# SAMV71_Xplained_Ultra_Shield_Connectors.net
KiCad netlist of a schematic drawn in Altium Designer
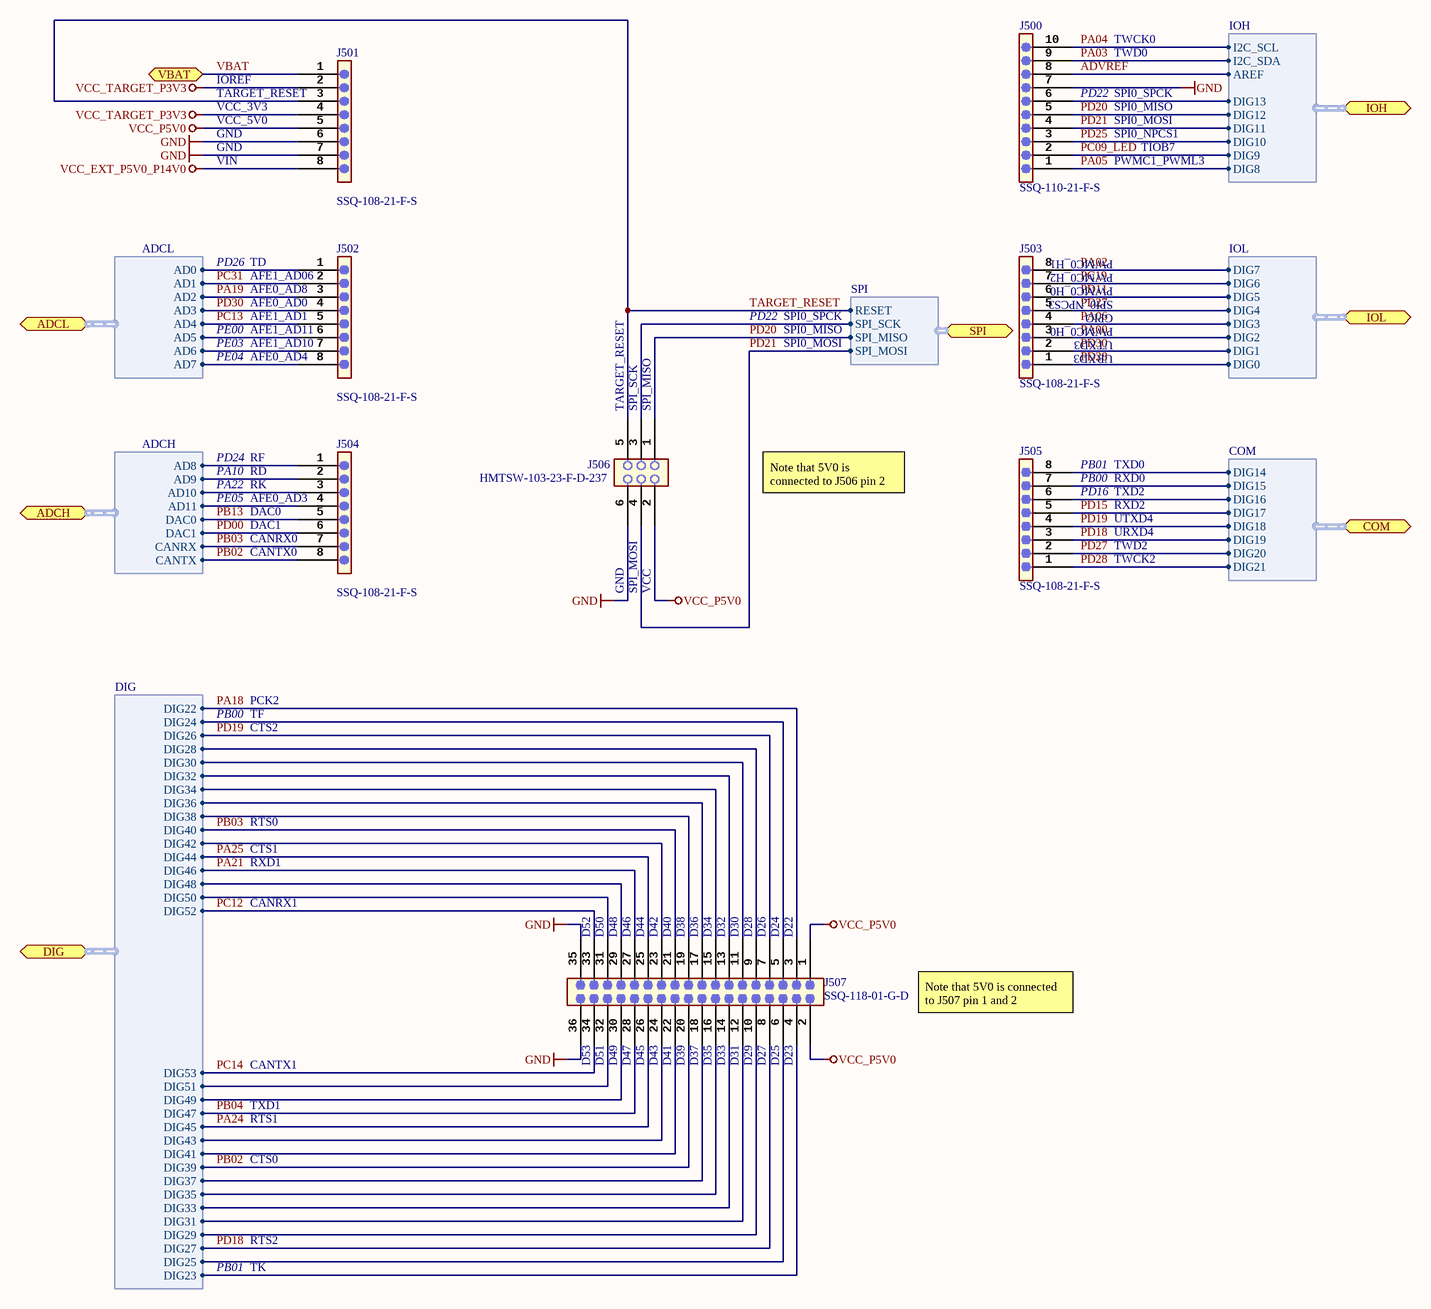
[diagram p0: SAMV71_Xplained_Ultra_Shield_Connectors.SchDoc]

(export (version "E")
  (design (tool "Eeschema 10.0.6"))
  (components
    (comp (ref "J500")
      (value "SSQ-110-21-F-S")
      (footprint "AP8-00822")
      (description "1x10 receptacle pin header, low insertion force, 2.54mm pitch THM, Pin in Paste")
      (fields (field (name "MANUFACTURER") "SAMTEC"))
      (libsource (lib "AltiumDbLib") (part "HEADER 1x10 FEMALE"))
    )
    (comp (ref "J501")
      (value "SSQ-108-21-F-S")
      (footprint "AP8-00823")
      (description "1x8 receptacle pin header, low insertion force, 2.54mm pitch THM, Pin in Paste")
      (fields (field (name "MANUFACTURER") "SAMTEC"))
      (libsource (lib "") (part "HEADER 1x8 FEMALE_1"))
    )
    (comp (ref "J502")
      (value "SSQ-108-21-F-S")
      (footprint "AP8-00823")
      (description "1x8 receptacle pin header, low insertion force, 2.54mm pitch THM, Pin in Paste")
      (fields (field (name "MANUFACTURER") "SAMTEC"))
      (libsource (lib "") (part "HEADER 1x8 FEMALE_1"))
    )
    (comp (ref "J503")
      (value "SSQ-108-21-F-S")
      (footprint "AP8-00823")
      (description "1x8 receptacle pin header, low insertion force, 2.54mm pitch THM, Pin in Paste")
      (fields (field (name "MANUFACTURER") "SAMTEC"))
      (libsource (lib "AltiumDbLib") (part "HEADER 1x8 FEMALE"))
    )
    (comp (ref "J504")
      (value "SSQ-108-21-F-S")
      (footprint "AP8-00823")
      (description "1x8 receptacle pin header, low insertion force, 2.54mm pitch THM, Pin in Paste")
      (fields (field (name "MANUFACTURER") "SAMTEC"))
      (libsource (lib "") (part "HEADER 1x8 FEMALE_1"))
    )
    (comp (ref "J505")
      (value "SSQ-108-21-F-S")
      (footprint "AP8-00823")
      (description "1x8 receptacle pin header, low insertion force, 2.54mm pitch THM, Pin in Paste")
      (fields (field (name "MANUFACTURER") "SAMTEC"))
      (libsource (lib "AltiumDbLib") (part "HEADER 1x8 FEMALE"))
    )
    (comp (ref "J506")
      (value "HMTSW-103-23-F-D-237")
      (footprint "AP8-00182")
      (description "2x3 pin header, 2.54mm pitch, Pin-in-Paste THM")
      (fields (field (name "MANUFACTURER") "SAMTEC"))
      (libsource (lib "AltiumDbLib") (part "HEADER 2x3"))
    )
    (comp (ref "J507")
      (value "SSQ-118-01-G-D")
      (footprint "AP8-00259")
      (description "2x18 female pin header, 2.54mm pitch, THM")
      (fields (field (name "MANUFACTURER") "SAMTEC"))
      (libsource (lib "AltiumDbLib") (part "HEADER 2x18 FEMALE"))
    )
  )
  (nets
    (net (code "8") (name "/AD0") (class "Default")
      (node (ref "J502") (pin "1") (pinfunction "1_1") (pintype "passive"))
    )
    (net (code "9") (name "/AD5") (class "Default")
      (node (ref "J502") (pin "6") (pinfunction "6_6") (pintype "passive"))
    )
    (net (code "10") (name "/AD6") (class "Default")
      (node (ref "J502") (pin "7") (pinfunction "7_7") (pintype "passive"))
    )
    (net (code "11") (name "/AD7") (class "Default")
      (node (ref "J502") (pin "8") (pinfunction "8_8") (pintype "passive"))
    )
    (net (code "12") (name "/AD8") (class "Default")
      (node (ref "J504") (pin "1") (pinfunction "1_1") (pintype "passive"))
    )
    (net (code "13") (name "/AD9") (class "Default")
      (node (ref "J504") (pin "2") (pinfunction "2_2") (pintype "passive"))
    )
    (net (code "14") (name "/AD10") (class "Default")
      (node (ref "J504") (pin "3") (pinfunction "3_3") (pintype "passive"))
    )
    (net (code "15") (name "/AD11") (class "Default")
      (node (ref "J504") (pin "4") (pinfunction "4_4") (pintype "passive"))
    )
    (net (code "16") (name "/ADVREF") (class "Default")
      (node (ref "J500") (pin "8") (pinfunction "8_8") (pintype "passive"))
    )
    (net (code "17") (name "/DIG13") (class "Default")
      (node (ref "J500") (pin "6") (pinfunction "6_6") (pintype "passive"))
    )
    (net (code "18") (name "/DIG14") (class "Default")
      (node (ref "J505") (pin "8") (pinfunction "8_8") (pintype "passive"))
    )
    (net (code "19") (name "/DIG15") (class "Default")
      (node (ref "J505") (pin "7") (pinfunction "7_7") (pintype "passive"))
    )
    (net (code "20") (name "/DIG16") (class "Default")
      (node (ref "J505") (pin "6") (pinfunction "6_6") (pintype "passive"))
    )
    (net (code "21") (name "/DIG23") (class "Default")
      (node (ref "J507") (pin "4") (pinfunction "4_4") (pintype "passive"))
    )
    (net (code "22") (name "/DIG24") (class "Default")
      (node (ref "J507") (pin "5") (pinfunction "5_5") (pintype "passive"))
    )
    (net (code "23") (name "/DIG25") (class "Default")
      (node (ref "J507") (pin "6") (pinfunction "6_6") (pintype "passive"))
    )
    (net (code "24") (name "/DIG28") (class "Default")
      (node (ref "J507") (pin "9") (pinfunction "9_9") (pintype "passive"))
    )
    (net (code "25") (name "/DIG29") (class "Default")
      (node (ref "J507") (pin "10") (pinfunction "10_10") (pintype "passive"))
    )
    (net (code "26") (name "/DIG30") (class "Default")
      (node (ref "J507") (pin "11") (pinfunction "11_11") (pintype "passive"))
    )
    (net (code "27") (name "/DIG31") (class "Default")
      (node (ref "J507") (pin "12") (pinfunction "12_12") (pintype "passive"))
    )
    (net (code "28") (name "/DIG32") (class "Default")
      (node (ref "J507") (pin "13") (pinfunction "13_13") (pintype "passive"))
    )
    (net (code "29") (name "/DIG33") (class "Default")
      (node (ref "J507") (pin "14") (pinfunction "14_14") (pintype "passive"))
    )
    (net (code "30") (name "/DIG34") (class "Default")
      (node (ref "J507") (pin "15") (pinfunction "15_15") (pintype "passive"))
    )
    (net (code "31") (name "/DIG35") (class "Default")
      (node (ref "J507") (pin "16") (pinfunction "16_16") (pintype "passive"))
    )
    (net (code "32") (name "/DIG36") (class "Default")
      (node (ref "J507") (pin "17") (pinfunction "17_17") (pintype "passive"))
    )
    (net (code "33") (name "/DIG37") (class "Default")
      (node (ref "J507") (pin "18") (pinfunction "18_18") (pintype "passive"))
    )
    (net (code "34") (name "/DIG38") (class "Default")
      (node (ref "J507") (pin "19") (pinfunction "19_19") (pintype "passive"))
    )
    (net (code "35") (name "/DIG41") (class "Default")
      (node (ref "J507") (pin "22") (pinfunction "22_22") (pintype "passive"))
    )
    (net (code "36") (name "/DIG42") (class "Default")
      (node (ref "J507") (pin "23") (pinfunction "23_23") (pintype "passive"))
    )
    (net (code "37") (name "/DIG43") (class "Default")
      (node (ref "J507") (pin "24") (pinfunction "24_24") (pintype "passive"))
    )
    (net (code "38") (name "/DIG48") (class "Default")
      (node (ref "J507") (pin "29") (pinfunction "29_29") (pintype "passive"))
    )
    (net (code "39") (name "/DIG49") (class "Default")
      (node (ref "J507") (pin "30") (pinfunction "30_30") (pintype "passive"))
    )
    (net (code "40") (name "/DIG50") (class "Default")
      (node (ref "J507") (pin "31") (pinfunction "31_31") (pintype "passive"))
    )
    (net (code "41") (name "/DIG51") (class "Default")
      (node (ref "J507") (pin "32") (pinfunction "32_32") (pintype "passive"))
    )
    (net (code "42") (name "/PA00") (class "Default")
      (node (ref "J503") (pin "3") (pinfunction "3_3") (pintype "passive"))
    )
    (net (code "43") (name "/PA02") (class "Default")
      (node (ref "J503") (pin "8") (pinfunction "8_8") (pintype "passive"))
    )
    (net (code "44") (name "/PA03") (class "Default")
      (node (ref "J500") (pin "9") (pinfunction "9_9") (pintype "passive"))
    )
    (net (code "45") (name "/PA04") (class "Default")
      (node (ref "J500") (pin "10") (pinfunction "10_10") (pintype "passive"))
    )
    (net (code "46") (name "/PA05") (class "Default")
      (node (ref "J500") (pin "1") (pinfunction "1_1") (pintype "passive"))
    )
    (net (code "47") (name "/PA06") (class "Default")
      (node (ref "J503") (pin "4") (pinfunction "4_4") (pintype "passive"))
    )
    (net (code "48") (name "/PA18") (class "Default")
      (node (ref "J507") (pin "3") (pinfunction "3_3") (pintype "passive"))
    )
    (net (code "49") (name "/PA19") (class "Default")
      (node (ref "J502") (pin "3") (pinfunction "3_3") (pintype "passive"))
    )
    (net (code "50") (name "/PA21") (class "Default")
      (node (ref "J507") (pin "27") (pinfunction "27_27") (pintype "passive"))
    )
    (net (code "51") (name "/PA24") (class "Default")
      (node (ref "J507") (pin "26") (pinfunction "26_26") (pintype "passive"))
    )
    (net (code "52") (name "/PA25") (class "Default")
      (node (ref "J507") (pin "25") (pinfunction "25_25") (pintype "passive"))
    )
    (net (code "53") (name "/PB02") (class "Default")
      (node (ref "J504") (pin "8") (pinfunction "8_8") (pintype "passive"))
      (node (ref "J507") (pin "20") (pinfunction "20_20") (pintype "passive"))
    )
    (net (code "54") (name "/PB03") (class "Default")
      (node (ref "J504") (pin "7") (pinfunction "7_7") (pintype "passive"))
      (node (ref "J507") (pin "21") (pinfunction "21_21") (pintype "passive"))
    )
    (net (code "55") (name "/PB04") (class "Default")
      (node (ref "J507") (pin "28") (pinfunction "28_28") (pintype "passive"))
    )
    (net (code "56") (name "/PB13") (class "Default")
      (node (ref "J504") (pin "5") (pinfunction "5_5") (pintype "passive"))
    )
    (net (code "57") (name "/PC09_LED") (class "Default")
      (node (ref "J500") (pin "2") (pinfunction "2_2") (pintype "passive"))
    )
    (net (code "58") (name "/PC12") (class "Default")
      (node (ref "J507") (pin "33") (pinfunction "33_33") (pintype "passive"))
    )
    (net (code "59") (name "/PC13") (class "Default")
      (node (ref "J502") (pin "5") (pinfunction "5_5") (pintype "passive"))
    )
    (net (code "60") (name "/PC14") (class "Default")
      (node (ref "J507") (pin "34") (pinfunction "34_34") (pintype "passive"))
    )
    (net (code "61") (name "/PC19") (class "Default")
      (node (ref "J503") (pin "7") (pinfunction "7_7") (pintype "passive"))
    )
    (net (code "62") (name "/PC31") (class "Default")
      (node (ref "J502") (pin "2") (pinfunction "2_2") (pintype "passive"))
    )
    (net (code "63") (name "/PD00") (class "Default")
      (node (ref "J504") (pin "6") (pinfunction "6_6") (pintype "passive"))
    )
    (net (code "64") (name "/PD11") (class "Default")
      (node (ref "J503") (pin "6") (pinfunction "6_6") (pintype "passive"))
    )
    (net (code "65") (name "/PD15") (class "Default")
      (node (ref "J505") (pin "5") (pinfunction "5_5") (pintype "passive"))
    )
    (net (code "66") (name "/PD18") (class "Default")
      (node (ref "J505") (pin "3") (pinfunction "3_3") (pintype "passive"))
      (node (ref "J507") (pin "8") (pinfunction "8_8") (pintype "passive"))
    )
    (net (code "67") (name "/PD19") (class "Default")
      (node (ref "J505") (pin "4") (pinfunction "4_4") (pintype "passive"))
      (node (ref "J507") (pin "7") (pinfunction "7_7") (pintype "passive"))
    )
    (net (code "68") (name "/PD20") (class "Default")
      (node (ref "J500") (pin "5") (pinfunction "5_5") (pintype "passive"))
      (node (ref "J506") (pin "1") (pinfunction "1_1") (pintype "passive"))
    )
    (net (code "69") (name "/PD21") (class "Default")
      (node (ref "J500") (pin "4") (pinfunction "4_4") (pintype "passive"))
      (node (ref "J506") (pin "4") (pinfunction "4_4") (pintype "passive"))
    )
    (net (code "70") (name "/PD25") (class "Default")
      (node (ref "J500") (pin "3") (pinfunction "3_3") (pintype "passive"))
    )
    (net (code "71") (name "/PD27") (class "Default")
      (node (ref "J503") (pin "5") (pinfunction "5_5") (pintype "passive"))
      (node (ref "J505") (pin "2") (pinfunction "2_2") (pintype "passive"))
    )
    (net (code "72") (name "/PD28") (class "Default")
      (node (ref "J503") (pin "1") (pinfunction "1_1") (pintype "passive"))
      (node (ref "J505") (pin "1") (pinfunction "1_1") (pintype "passive"))
    )
    (net (code "73") (name "/PD30") (class "Default")
      (node (ref "J502") (pin "4") (pinfunction "4_4") (pintype "passive"))
      (node (ref "J503") (pin "2") (pinfunction "2_2") (pintype "passive"))
    )
    (net (code "74") (name "/SPI_SCK") (class "Default")
      (node (ref "J506") (pin "3") (pinfunction "3_3") (pintype "passive"))
    )
    (net (code "75") (name "/TARGET_RESET") (class "Default")
      (node (ref "J501") (pin "3") (pinfunction "3_3") (pintype "passive"))
      (node (ref "J506") (pin "5") (pinfunction "5_5") (pintype "passive"))
    )
    (net (code "76") (name "/VBAT") (class "Default")
      (node (ref "J501") (pin "1") (pinfunction "1_1") (pintype "passive"))
    )
    (net (code "84") (name "GND") (class "Default")
      (node (ref "J500") (pin "7") (pinfunction "7_7") (pintype "passive"))
      (node (ref "J501") (pin "6") (pinfunction "6_6") (pintype "passive"))
      (node (ref "J501") (pin "7") (pinfunction "7_7") (pintype "passive"))
      (node (ref "J506") (pin "6") (pinfunction "6_6") (pintype "passive"))
      (node (ref "J507") (pin "35") (pinfunction "35_35") (pintype "passive"))
      (node (ref "J507") (pin "36") (pinfunction "36_36") (pintype "passive"))
    )
    (net (code "85") (name "VCC_EXT_P5V0_P14V0") (class "Default")
      (node (ref "J501") (pin "8") (pinfunction "8_8") (pintype "passive"))
    )
    (net (code "86") (name "VCC_P5V0") (class "Default")
      (node (ref "J501") (pin "5") (pinfunction "5_5") (pintype "passive"))
      (node (ref "J506") (pin "2") (pinfunction "2_2") (pintype "passive"))
      (node (ref "J507") (pin "1") (pinfunction "1_1") (pintype "passive"))
      (node (ref "J507") (pin "2") (pinfunction "2_2") (pintype "passive"))
    )
    (net (code "87") (name "VCC_TARGET_P3V3") (class "Default")
      (node (ref "J501") (pin "2") (pinfunction "2_2") (pintype "passive"))
      (node (ref "J501") (pin "4") (pinfunction "4_4") (pintype "passive"))
    )
  )
)
